# scale-slave.net
KiCad netlist of a schematic drawn in EAGLE
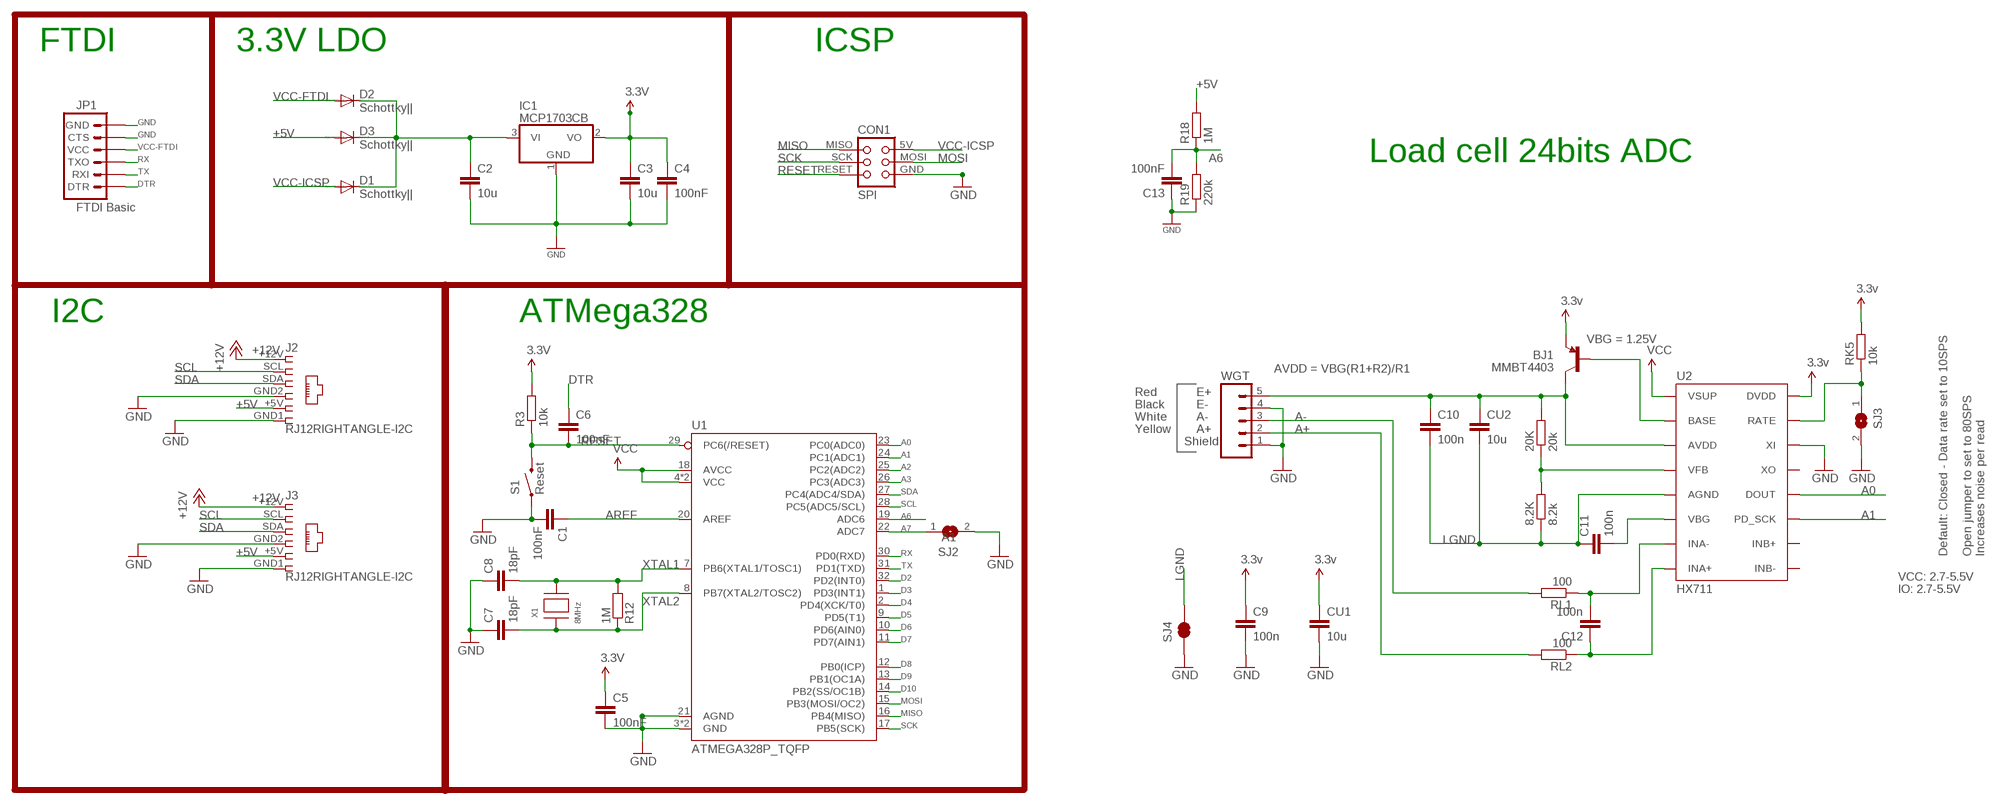
[diagram p0: schematic, sheet 1]

(export (version "E")
  (design (tool "Eeschema 10.0.6"))
  (components
    (comp (ref "8.2K")
      (value "8.2k")
      (footprint "eagle-import:M0805")
      (libsource (lib "eagle-import") (part "resistor_R-EU_M0805"))
    )
    (comp (ref "20K")
      (value "20k")
      (footprint "eagle-import:M0805")
      (libsource (lib "eagle-import") (part "resistor_R-EU_M0805"))
    )
    (comp (ref "BJ1")
      (value "MMBT4403")
      (footprint "eagle-import:SOT23-3")
      (libsource (lib "eagle-import") (part "TRANSISTOR_PNPMMBT4403"))
    )
    (comp (ref "C1")
      (value "100nF")
      (footprint "eagle-import:C0805K")
      (fields (field (name "MPN") "80-C1206C104K5R"))
      (libsource (lib "eagle-import") (part "rcl_334_C-EUC0805K"))
    )
    (comp (ref "C2")
      (value "10u")
      (footprint "eagle-import:C0805K")
      (fields (field (name "MPN") "77-VJ1206V106ZXQTBC"))
      (libsource (lib "eagle-import") (part "rcl_334_C-EUC0805K"))
    )
    (comp (ref "C3")
      (value "10u")
      (footprint "eagle-import:C0805K")
      (fields (field (name "MPN") "77-VJ1206V106ZXQTBC"))
      (libsource (lib "eagle-import") (part "rcl_334_C-EUC0805K"))
    )
    (comp (ref "C4")
      (value "100nF")
      (footprint "eagle-import:C0805K")
      (fields (field (name "MPN") "80-C1206C104K5R"))
      (libsource (lib "eagle-import") (part "rcl_334_C-EUC0805K"))
    )
    (comp (ref "C5")
      (value "100nF")
      (footprint "eagle-import:C0805K")
      (fields (field (name "MPN") "80-C1206C104K5R"))
      (libsource (lib "eagle-import") (part "rcl_334_C-EUC0805K"))
    )
    (comp (ref "C6")
      (value "100nF")
      (footprint "eagle-import:C0805K")
      (fields (field (name "MPN") "80-C1206C104K5R"))
      (libsource (lib "eagle-import") (part "rcl_334_C-EUC0805K"))
    )
    (comp (ref "C7")
      (value "18pF")
      (footprint "eagle-import:C0805K")
      (fields (field (name "MPN") "77-VJ1206A180JXXPBC"))
      (libsource (lib "eagle-import") (part "rcl_334_C-EUC0805K"))
    )
    (comp (ref "C8")
      (value "18pF")
      (footprint "eagle-import:C0805K")
      (fields (field (name "MPN") "77-VJ1206A180JXXPBC"))
      (libsource (lib "eagle-import") (part "rcl_334_C-EUC0805K"))
    )
    (comp (ref "C9")
      (value "100n")
      (footprint "eagle-import:C0805")
      (libsource (lib "eagle-import") (part "C-EUC0805"))
    )
    (comp (ref "C10")
      (value "100n")
      (footprint "eagle-import:C0805")
      (libsource (lib "eagle-import") (part "C-EUC0805"))
    )
    (comp (ref "C11")
      (value "100n")
      (footprint "eagle-import:C0805")
      (libsource (lib "eagle-import") (part "C-EUC0805"))
    )
    (comp (ref "C12")
      (value "100n")
      (footprint "eagle-import:C0805")
      (libsource (lib "eagle-import") (part "C-EUC0805"))
    )
    (comp (ref "C13")
      (value "100nF")
      (footprint "eagle-import:C0805K")
      (fields (field (name "MPN") "80-C1206C104K5R"))
      (libsource (lib "eagle-import") (part "rcl_334_C-EUC0805K"))
    )
    (comp (ref "CON1")
      (value "SPI")
      (footprint "eagle-import:TC2030-MCP")
      (libsource (lib "eagle-import") (part "TINYISPTAG"))
    )
    (comp (ref "CU1")
      (value "10u")
      (footprint "eagle-import:C0805")
      (libsource (lib "eagle-import") (part "C-EUC0805"))
    )
    (comp (ref "CU2")
      (value "10u")
      (footprint "eagle-import:C0805")
      (libsource (lib "eagle-import") (part "C-EUC0805"))
    )
    (comp (ref "D1")
      (value "Schottky||")
      (footprint "eagle-import:SOD123")
      (fields (field (name "MPN") "621-1N5819HW-F"))
      (libsource (lib "eagle-import") (part "MBR0520LT"))
    )
    (comp (ref "D2")
      (value "Schottky||")
      (footprint "eagle-import:SOD123")
      (fields (field (name "MPN") "621-1N5819HW-F"))
      (libsource (lib "eagle-import") (part "MBR0520LT"))
    )
    (comp (ref "D3")
      (value "Schottky||")
      (footprint "eagle-import:SOD123")
      (fields (field (name "MPN") "621-1N5819HW-F"))
      (libsource (lib "eagle-import") (part "MBR0520LT"))
    )
    (comp (ref "IC1")
      (value "MCP1703CB")
      (footprint "eagle-import:SOT23")
      (libsource (lib "eagle-import") (part "MCP1703CB"))
    )
    (comp (ref "J2")
      (value "RJ12RIGHTANGLE-I2C")
      (footprint "eagle-import:RJ12-RIGHTANGLE-I2C")
      (libsource (lib "eagle-import") (part "RJ12RIGHTANGLE-I2C"))
    )
    (comp (ref "J3")
      (value "RJ12RIGHTANGLE-I2C")
      (footprint "eagle-import:RJ12-RIGHTANGLE-I2C")
      (libsource (lib "eagle-import") (part "RJ12RIGHTANGLE-I2C"))
    )
    (comp (ref "JP1")
      (value "FTDI Basic")
      (footprint "eagle-import:1X06")
      (libsource (lib "eagle-import") (part "ARDUINO_SERIAL_PROGRAMPTH"))
    )
    (comp (ref "R3")
      (value "10k")
      (footprint "eagle-import:R0805")
      (libsource (lib "eagle-import") (part "R-EU_R0805"))
    )
    (comp (ref "R12")
      (value "1M")
      (footprint "eagle-import:R0805")
      (libsource (lib "eagle-import") (part "R-EU_R0805"))
    )
    (comp (ref "R18")
      (value "1M")
      (footprint "eagle-import:R0805")
      (libsource (lib "eagle-import") (part "R-EU_R0805"))
    )
    (comp (ref "R19")
      (value "220k")
      (footprint "eagle-import:R0805")
      (libsource (lib "eagle-import") (part "R-EU_R0805"))
    )
    (comp (ref "RK5")
      (value "10k")
      (footprint "eagle-import:M0805")
      (libsource (lib "eagle-import") (part "resistor_R-EU_M0805"))
    )
    (comp (ref "RL1")
      (value "100")
      (footprint "eagle-import:M0805")
      (libsource (lib "eagle-import") (part "resistor_R-EU_M0805"))
    )
    (comp (ref "RL2")
      (value "100")
      (footprint "eagle-import:M0805")
      (libsource (lib "eagle-import") (part "resistor_R-EU_M0805"))
    )
    (comp (ref "S1")
      (value "Reset")
      (footprint "eagle-import:TACTILE-SWITCH-SMD-ALT01")
      (libsource (lib "eagle-import") (part "SWITCH-MOMENTARY-2SMD-ALT01"))
    )
    (comp (ref "SJ2")
      (value "A1")
      (footprint "eagle-import:SJ")
      (libsource (lib "eagle-import") (part "jumper_252_SJ"))
    )
    (comp (ref "SJ3") (value "SJ") (footprint "eagle-import:SJ") (libsource (lib "eagle-import") (part "SJ")))
    (comp (ref "SJ4")
      (value "JUMPER-PAD-2-NC_BY_TRACE")
      (footprint "eagle-import:PAD-JUMPER-2-NC_BY_TRACE_YES_SILK")
      (libsource (lib "eagle-import") (part "JUMPER-PAD-2-NC_BY_TRACE"))
    )
    (comp (ref "U1")
      (value "ATMEGA328P_TQFP")
      (footprint "eagle-import:TQFP32-08")
      (libsource (lib "eagle-import") (part "ATMEGA328P_TQFP"))
    )
    (comp (ref "U2")
      (value "HX711")
      (footprint "eagle-import:SO16")
      (libsource (lib "eagle-import") (part "HX711HX711"))
    )
    (comp (ref "WGT")
      (value "M05PTH")
      (footprint "eagle-import:1X05")
      (libsource (lib "eagle-import") (part "M05PTH"))
    )
    (comp (ref "X1")
      (value "8MHz")
      (footprint "eagle-import:NX6035")
      (fields (field (name "MPN") "729-F60800010"))
      (libsource (lib "eagle-import") (part "XTALNX6035"))
    )
  )
  (nets
    (net (code "1") (name "+12V") (class "Default")
      (node (ref "J2") (pin "+12V") (pinfunction "1_+12V") (pintype "bidirectional"))
      (node (ref "J3") (pin "+12V") (pinfunction "1_+12V") (pintype "bidirectional"))
    )
    (net (code "2") (name "/+5V") (class "Default")
      (node (ref "D3") (pin "A") (pinfunction "A_A") (pintype "passive"))
      (node (ref "J2") (pin "+5V") (pinfunction "5_+5V") (pintype "bidirectional"))
      (node (ref "J3") (pin "+5V") (pinfunction "5_+5V") (pintype "bidirectional"))
      (node (ref "R18") (pin "2") (pinfunction "2_2") (pintype "passive"))
    )
    (net (code "3") (name "/A+") (class "Default")
      (node (ref "RL2") (pin "2") (pinfunction "2_2") (pintype "passive"))
      (node (ref "WGT") (pin "2") (pinfunction "2_2") (pintype "passive"))
    )
    (net (code "4") (name "/A-") (class "Default")
      (node (ref "RL1") (pin "2") (pinfunction "2_2") (pintype "passive"))
      (node (ref "WGT") (pin "3") (pinfunction "3_3") (pintype "passive"))
    )
    (net (code "5") (name "/A0") (class "Default")
      (node (ref "U1") (pin "23") (pinfunction "PC0(ADC0)_23") (pintype "bidirectional"))
      (node (ref "U2") (pin "12") (pinfunction "DOUT_12") (pintype "bidirectional"))
    )
    (net (code "6") (name "/A1") (class "Default")
      (node (ref "U1") (pin "24") (pinfunction "PC1(ADC1)_24") (pintype "bidirectional"))
      (node (ref "U2") (pin "11") (pinfunction "PD_SCK_11") (pintype "bidirectional"))
    )
    (net (code "7") (name "/A2") (class "Default")
      (node (ref "U1") (pin "25") (pinfunction "PC2(ADC2)_25") (pintype "bidirectional"))
    )
    (net (code "8") (name "/A3") (class "Default")
      (node (ref "U1") (pin "26") (pinfunction "PC3(ADC3)_26") (pintype "bidirectional"))
    )
    (net (code "9") (name "/A6") (class "Default")
      (node (ref "C13") (pin "2") (pinfunction "2_2") (pintype "passive"))
      (node (ref "R18") (pin "1") (pinfunction "1_1") (pintype "passive"))
      (node (ref "R19") (pin "2") (pinfunction "2_2") (pintype "passive"))
      (node (ref "U1") (pin "19") (pinfunction "ADC6_19") (pintype "bidirectional"))
    )
    (net (code "10") (name "/A7") (class "Default")
      (node (ref "SJ2") (pin "1") (pinfunction "1_1") (pintype "passive"))
      (node (ref "U1") (pin "22") (pinfunction "ADC7_22") (pintype "bidirectional"))
    )
    (net (code "11") (name "/AREF") (class "Default")
      (node (ref "C1") (pin "1") (pinfunction "1_1") (pintype "passive"))
      (node (ref "U1") (pin "20") (pinfunction "AREF_20") (pintype "bidirectional"))
    )
    (net (code "12") (name "/D2") (class "Default")
      (node (ref "U1") (pin "32") (pinfunction "PD2(INT0)_32") (pintype "bidirectional"))
    )
    (net (code "13") (name "/D3") (class "Default")
      (node (ref "U1") (pin "1") (pinfunction "PD3(INT1)_1") (pintype "bidirectional"))
    )
    (net (code "14") (name "/D4") (class "Default")
      (node (ref "U1") (pin "2") (pinfunction "PD4(XCK/T0)_2") (pintype "bidirectional"))
    )
    (net (code "15") (name "/D5") (class "Default")
      (node (ref "U1") (pin "9") (pinfunction "PD5(T1)_9") (pintype "bidirectional"))
    )
    (net (code "16") (name "/D6") (class "Default")
      (node (ref "U1") (pin "10") (pinfunction "PD6(AIN0)_10") (pintype "bidirectional"))
    )
    (net (code "17") (name "/D7") (class "Default")
      (node (ref "U1") (pin "11") (pinfunction "PD7(AIN1)_11") (pintype "bidirectional"))
    )
    (net (code "18") (name "/D8") (class "Default")
      (node (ref "U1") (pin "12") (pinfunction "PB0(ICP)_12") (pintype "bidirectional"))
    )
    (net (code "19") (name "/D9") (class "Default")
      (node (ref "U1") (pin "13") (pinfunction "PB1(OC1A)_13") (pintype "bidirectional"))
    )
    (net (code "20") (name "/D10") (class "Default")
      (node (ref "U1") (pin "14") (pinfunction "PB2(SS/OC1B)_14") (pintype "bidirectional"))
    )
    (net (code "21") (name "/DTR") (class "Default")
      (node (ref "C6") (pin "1") (pinfunction "1_1") (pintype "passive"))
      (node (ref "JP1") (pin "1") (pinfunction "DTR_1") (pintype "passive"))
    )
    (net (code "22") (name "/LGND") (class "Default")
      (node (ref "8.2K") (pin "1") (pinfunction "1_1") (pintype "passive"))
      (node (ref "C10") (pin "2") (pinfunction "2_2") (pintype "passive"))
      (node (ref "C11") (pin "1") (pinfunction "1_1") (pintype "passive"))
      (node (ref "CU2") (pin "2") (pinfunction "2_2") (pintype "passive"))
      (node (ref "SJ4") (pin "2") (pinfunction "2_2") (pintype "passive"))
      (node (ref "U2") (pin "5") (pinfunction "AGND_5") (pintype "bidirectional"))
    )
    (net (code "23") (name "/MISO") (class "Default")
      (node (ref "CON1") (pin "MISO") (pinfunction "MISO_MISO") (pintype "passive"))
      (node (ref "U1") (pin "16") (pinfunction "PB4(MISO)_16") (pintype "bidirectional"))
    )
    (net (code "24") (name "/MOSI") (class "Default")
      (node (ref "CON1") (pin "MOSI") (pinfunction "MOSI_MOSI") (pintype "passive"))
      (node (ref "U1") (pin "15") (pinfunction "PB3(MOSI/OC2)_15") (pintype "bidirectional"))
    )
    (net (code "25") (name "/RESET") (class "Default")
      (node (ref "C6") (pin "2") (pinfunction "2_2") (pintype "passive"))
      (node (ref "CON1") (pin "RESET") (pinfunction "RESET_RESET") (pintype "passive"))
      (node (ref "R3") (pin "1") (pinfunction "1_1") (pintype "passive"))
      (node (ref "S1") (pin "3") (pinfunction "2_3") (pintype "passive"))
      (node (ref "S1") (pin "4") (pinfunction "2_4") (pintype "passive"))
      (node (ref "U1") (pin "29") (pinfunction "PC6(/RESET)_29") (pintype "bidirectional"))
    )
    (net (code "26") (name "/RX") (class "Default")
      (node (ref "JP1") (pin "3") (pinfunction "TXO_3") (pintype "passive"))
      (node (ref "U1") (pin "30") (pinfunction "PD0(RXD)_30") (pintype "bidirectional"))
    )
    (net (code "27") (name "/SCK") (class "Default")
      (node (ref "CON1") (pin "SCK") (pinfunction "SCK_SCK") (pintype "passive"))
      (node (ref "U1") (pin "17") (pinfunction "PB5(SCK)_17") (pintype "bidirectional"))
    )
    (net (code "28") (name "/SCL") (class "Default")
      (node (ref "J2") (pin "SCL") (pinfunction "2_SCL") (pintype "bidirectional"))
      (node (ref "J3") (pin "SCL") (pinfunction "2_SCL") (pintype "bidirectional"))
      (node (ref "U1") (pin "28") (pinfunction "PC5(ADC5/SCL)_28") (pintype "bidirectional"))
    )
    (net (code "29") (name "/SDA") (class "Default")
      (node (ref "J2") (pin "SDA") (pinfunction "3_SDA") (pintype "bidirectional"))
      (node (ref "J3") (pin "SDA") (pinfunction "3_SDA") (pintype "bidirectional"))
      (node (ref "U1") (pin "27") (pinfunction "PC4(ADC4/SDA)_27") (pintype "bidirectional"))
    )
    (net (code "30") (name "/TX") (class "Default")
      (node (ref "JP1") (pin "2") (pinfunction "RXI_2") (pintype "passive"))
      (node (ref "U1") (pin "31") (pinfunction "PD1(TXD)_31") (pintype "bidirectional"))
    )
    (net (code "31") (name "/VCC-FTDI") (class "Default")
      (node (ref "D2") (pin "A") (pinfunction "A_A") (pintype "passive"))
      (node (ref "JP1") (pin "4") (pinfunction "VCC_4") (pintype "passive"))
    )
    (net (code "32") (name "/VCC-ICSP") (class "Default")
      (node (ref "CON1") (pin "5V") (pinfunction "VCC_5V") (pintype "passive"))
      (node (ref "D1") (pin "A") (pinfunction "A_A") (pintype "passive"))
    )
    (net (code "33") (name "/XTAL1") (class "Default")
      (node (ref "C8") (pin "2") (pinfunction "2_2") (pintype "passive"))
      (node (ref "R12") (pin "2") (pinfunction "2_2") (pintype "passive"))
      (node (ref "U1") (pin "7") (pinfunction "PB6(XTAL1/TOSC1)_7") (pintype "bidirectional"))
      (node (ref "X1") (pin "P$2") (pinfunction "P$2_P$2") (pintype "bidirectional"))
    )
    (net (code "34") (name "/XTAL2") (class "Default")
      (node (ref "C7") (pin "2") (pinfunction "2_2") (pintype "passive"))
      (node (ref "R12") (pin "1") (pinfunction "1_1") (pintype "passive"))
      (node (ref "U1") (pin "8") (pinfunction "PB7(XTAL2/TOSC2)_8") (pintype "bidirectional"))
      (node (ref "X1") (pin "P$1") (pinfunction "P$1_P$1") (pintype "bidirectional"))
    )
    (net (code "35") (name "3.3V") (class "Default")
      (node (ref "BJ1") (pin "2") (pinfunction "E_2") (pintype "passive"))
      (node (ref "C3") (pin "1") (pinfunction "1_1") (pintype "passive"))
      (node (ref "C4") (pin "1") (pinfunction "1_1") (pintype "passive"))
      (node (ref "C5") (pin "1") (pinfunction "1_1") (pintype "passive"))
      (node (ref "C9") (pin "1") (pinfunction "1_1") (pintype "passive"))
      (node (ref "CU1") (pin "1") (pinfunction "1_1") (pintype "passive"))
      (node (ref "IC1") (pin "2") (pinfunction "VO_2") (pintype "passive"))
      (node (ref "R3") (pin "2") (pinfunction "2_2") (pintype "passive"))
      (node (ref "RK5") (pin "2") (pinfunction "2_2") (pintype "passive"))
      (node (ref "U1") (pin "18") (pinfunction "AVCC_18") (pintype "bidirectional"))
      (node (ref "U1") (pin "4") (pinfunction "VCC_4") (pintype "bidirectional"))
      (node (ref "U1") (pin "6") (pinfunction "VCC_6") (pintype "bidirectional"))
      (node (ref "U2") (pin "1") (pinfunction "VSUP_1") (pintype "bidirectional"))
      (node (ref "U2") (pin "16") (pinfunction "DVDD_16") (pintype "bidirectional"))
    )
    (net (code "36") (name "GND") (class "Default")
      (node (ref "C1") (pin "2") (pinfunction "2_2") (pintype "passive"))
      (node (ref "C13") (pin "1") (pinfunction "1_1") (pintype "passive"))
      (node (ref "C2") (pin "2") (pinfunction "2_2") (pintype "passive"))
      (node (ref "C3") (pin "2") (pinfunction "2_2") (pintype "passive"))
      (node (ref "C4") (pin "2") (pinfunction "2_2") (pintype "passive"))
      (node (ref "C5") (pin "2") (pinfunction "2_2") (pintype "passive"))
      (node (ref "C7") (pin "1") (pinfunction "1_1") (pintype "passive"))
      (node (ref "C8") (pin "1") (pinfunction "1_1") (pintype "passive"))
      (node (ref "C9") (pin "2") (pinfunction "2_2") (pintype "passive"))
      (node (ref "CON1") (pin "GND") (pinfunction "GND_GND") (pintype "passive"))
      (node (ref "CU1") (pin "2") (pinfunction "2_2") (pintype "passive"))
      (node (ref "IC1") (pin "1") (pinfunction "GND_1") (pintype "passive"))
      (node (ref "J2") (pin "GND1") (pinfunction "6_GND1") (pintype "bidirectional"))
      (node (ref "J2") (pin "GND2") (pinfunction "4_GND2") (pintype "bidirectional"))
      (node (ref "J3") (pin "GND1") (pinfunction "6_GND1") (pintype "bidirectional"))
      (node (ref "J3") (pin "GND2") (pinfunction "4_GND2") (pintype "bidirectional"))
      (node (ref "JP1") (pin "5") (pinfunction "CTS_5") (pintype "passive"))
      (node (ref "JP1") (pin "6") (pinfunction "GND_6") (pintype "passive"))
      (node (ref "R19") (pin "1") (pinfunction "1_1") (pintype "passive"))
      (node (ref "S1") (pin "1") (pinfunction "1_1") (pintype "passive"))
      (node (ref "S1") (pin "2") (pinfunction "1_2") (pintype "passive"))
      (node (ref "SJ2") (pin "2") (pinfunction "2_2") (pintype "passive"))
      (node (ref "SJ3") (pin "2") (pinfunction "2_2") (pintype "passive"))
      (node (ref "SJ4") (pin "1") (pinfunction "1_1") (pintype "passive"))
      (node (ref "U1") (pin "21") (pinfunction "AGND_21") (pintype "bidirectional"))
      (node (ref "U1") (pin "3") (pinfunction "GND_3") (pintype "bidirectional"))
      (node (ref "U1") (pin "5") (pinfunction "GND_5") (pintype "bidirectional"))
      (node (ref "U2") (pin "14") (pinfunction "XI_14") (pintype "bidirectional"))
      (node (ref "WGT") (pin "1") (pinfunction "1_1") (pintype "passive"))
      (node (ref "WGT") (pin "4") (pinfunction "4_4") (pintype "passive"))
    )
    (net (code "37") (name "Net-(BJ1-B)") (class "Default")
      (node (ref "BJ1") (pin "1") (pinfunction "B_1") (pintype "passive"))
      (node (ref "U2") (pin "2") (pinfunction "BASE_2") (pintype "bidirectional"))
    )
    (net (code "38") (name "Net-(BJ1-C)") (class "Default")
      (node (ref "20K") (pin "2") (pinfunction "2_2") (pintype "passive"))
      (node (ref "BJ1") (pin "3") (pinfunction "C_3") (pintype "passive"))
      (node (ref "C10") (pin "1") (pinfunction "1_1") (pintype "passive"))
      (node (ref "CU2") (pin "1") (pinfunction "1_1") (pintype "passive"))
      (node (ref "U2") (pin "3") (pinfunction "AVDD_3") (pintype "bidirectional"))
      (node (ref "WGT") (pin "5") (pinfunction "5_5") (pintype "passive"))
    )
    (net (code "39") (name "Net-(IC1-VI)") (class "Default")
      (node (ref "C2") (pin "1") (pinfunction "1_1") (pintype "passive"))
      (node (ref "D1") (pin "C") (pinfunction "C_C") (pintype "passive"))
      (node (ref "D2") (pin "C") (pinfunction "C_C") (pintype "passive"))
      (node (ref "D3") (pin "C") (pinfunction "C_C") (pintype "passive"))
      (node (ref "IC1") (pin "3") (pinfunction "VI_3") (pintype "input"))
    )
    (net (code "40") (name "Net-(U2-INA+)") (class "Default")
      (node (ref "C12") (pin "1") (pinfunction "1_1") (pintype "passive"))
      (node (ref "RL2") (pin "1") (pinfunction "1_1") (pintype "passive"))
      (node (ref "U2") (pin "8") (pinfunction "INA+_8") (pintype "bidirectional"))
    )
    (net (code "41") (name "Net-(U2-INA-)") (class "Default")
      (node (ref "C12") (pin "2") (pinfunction "2_2") (pintype "passive"))
      (node (ref "RL1") (pin "1") (pinfunction "1_1") (pintype "passive"))
      (node (ref "U2") (pin "7") (pinfunction "INA-_7") (pintype "bidirectional"))
    )
    (net (code "42") (name "Net-(U2-RATE)") (class "Default")
      (node (ref "RK5") (pin "1") (pinfunction "1_1") (pintype "passive"))
      (node (ref "SJ3") (pin "1") (pinfunction "1_1") (pintype "passive"))
      (node (ref "U2") (pin "15") (pinfunction "RATE_15") (pintype "bidirectional"))
    )
    (net (code "43") (name "Net-(U2-VBG)") (class "Default")
      (node (ref "C11") (pin "2") (pinfunction "2_2") (pintype "passive"))
      (node (ref "U2") (pin "6") (pinfunction "VBG_6") (pintype "bidirectional"))
    )
    (net (code "44") (name "Net-(U2-VFB)") (class "Default")
      (node (ref "20K") (pin "1") (pinfunction "1_1") (pintype "passive"))
      (node (ref "8.2K") (pin "2") (pinfunction "2_2") (pintype "passive"))
      (node (ref "U2") (pin "4") (pinfunction "VFB_4") (pintype "bidirectional"))
    )
    (net (code "45") (name "unconnected-(U2-INB+-Pad10)") (class "Default")
      (node (ref "U2") (pin "10") (pinfunction "INB+_10") (pintype "bidirectional"))
    )
    (net (code "46") (name "unconnected-(U2-INB--Pad9)") (class "Default")
      (node (ref "U2") (pin "9") (pinfunction "INB-_9") (pintype "bidirectional"))
    )
    (net (code "47") (name "unconnected-(U2-XO-Pad13)") (class "Default")
      (node (ref "U2") (pin "13") (pinfunction "XO_13") (pintype "bidirectional"))
    )
  )
)
